# SCH_Patent-File_2025-01-08.net
KiCad netlist of a schematic drawn in EasyEDA
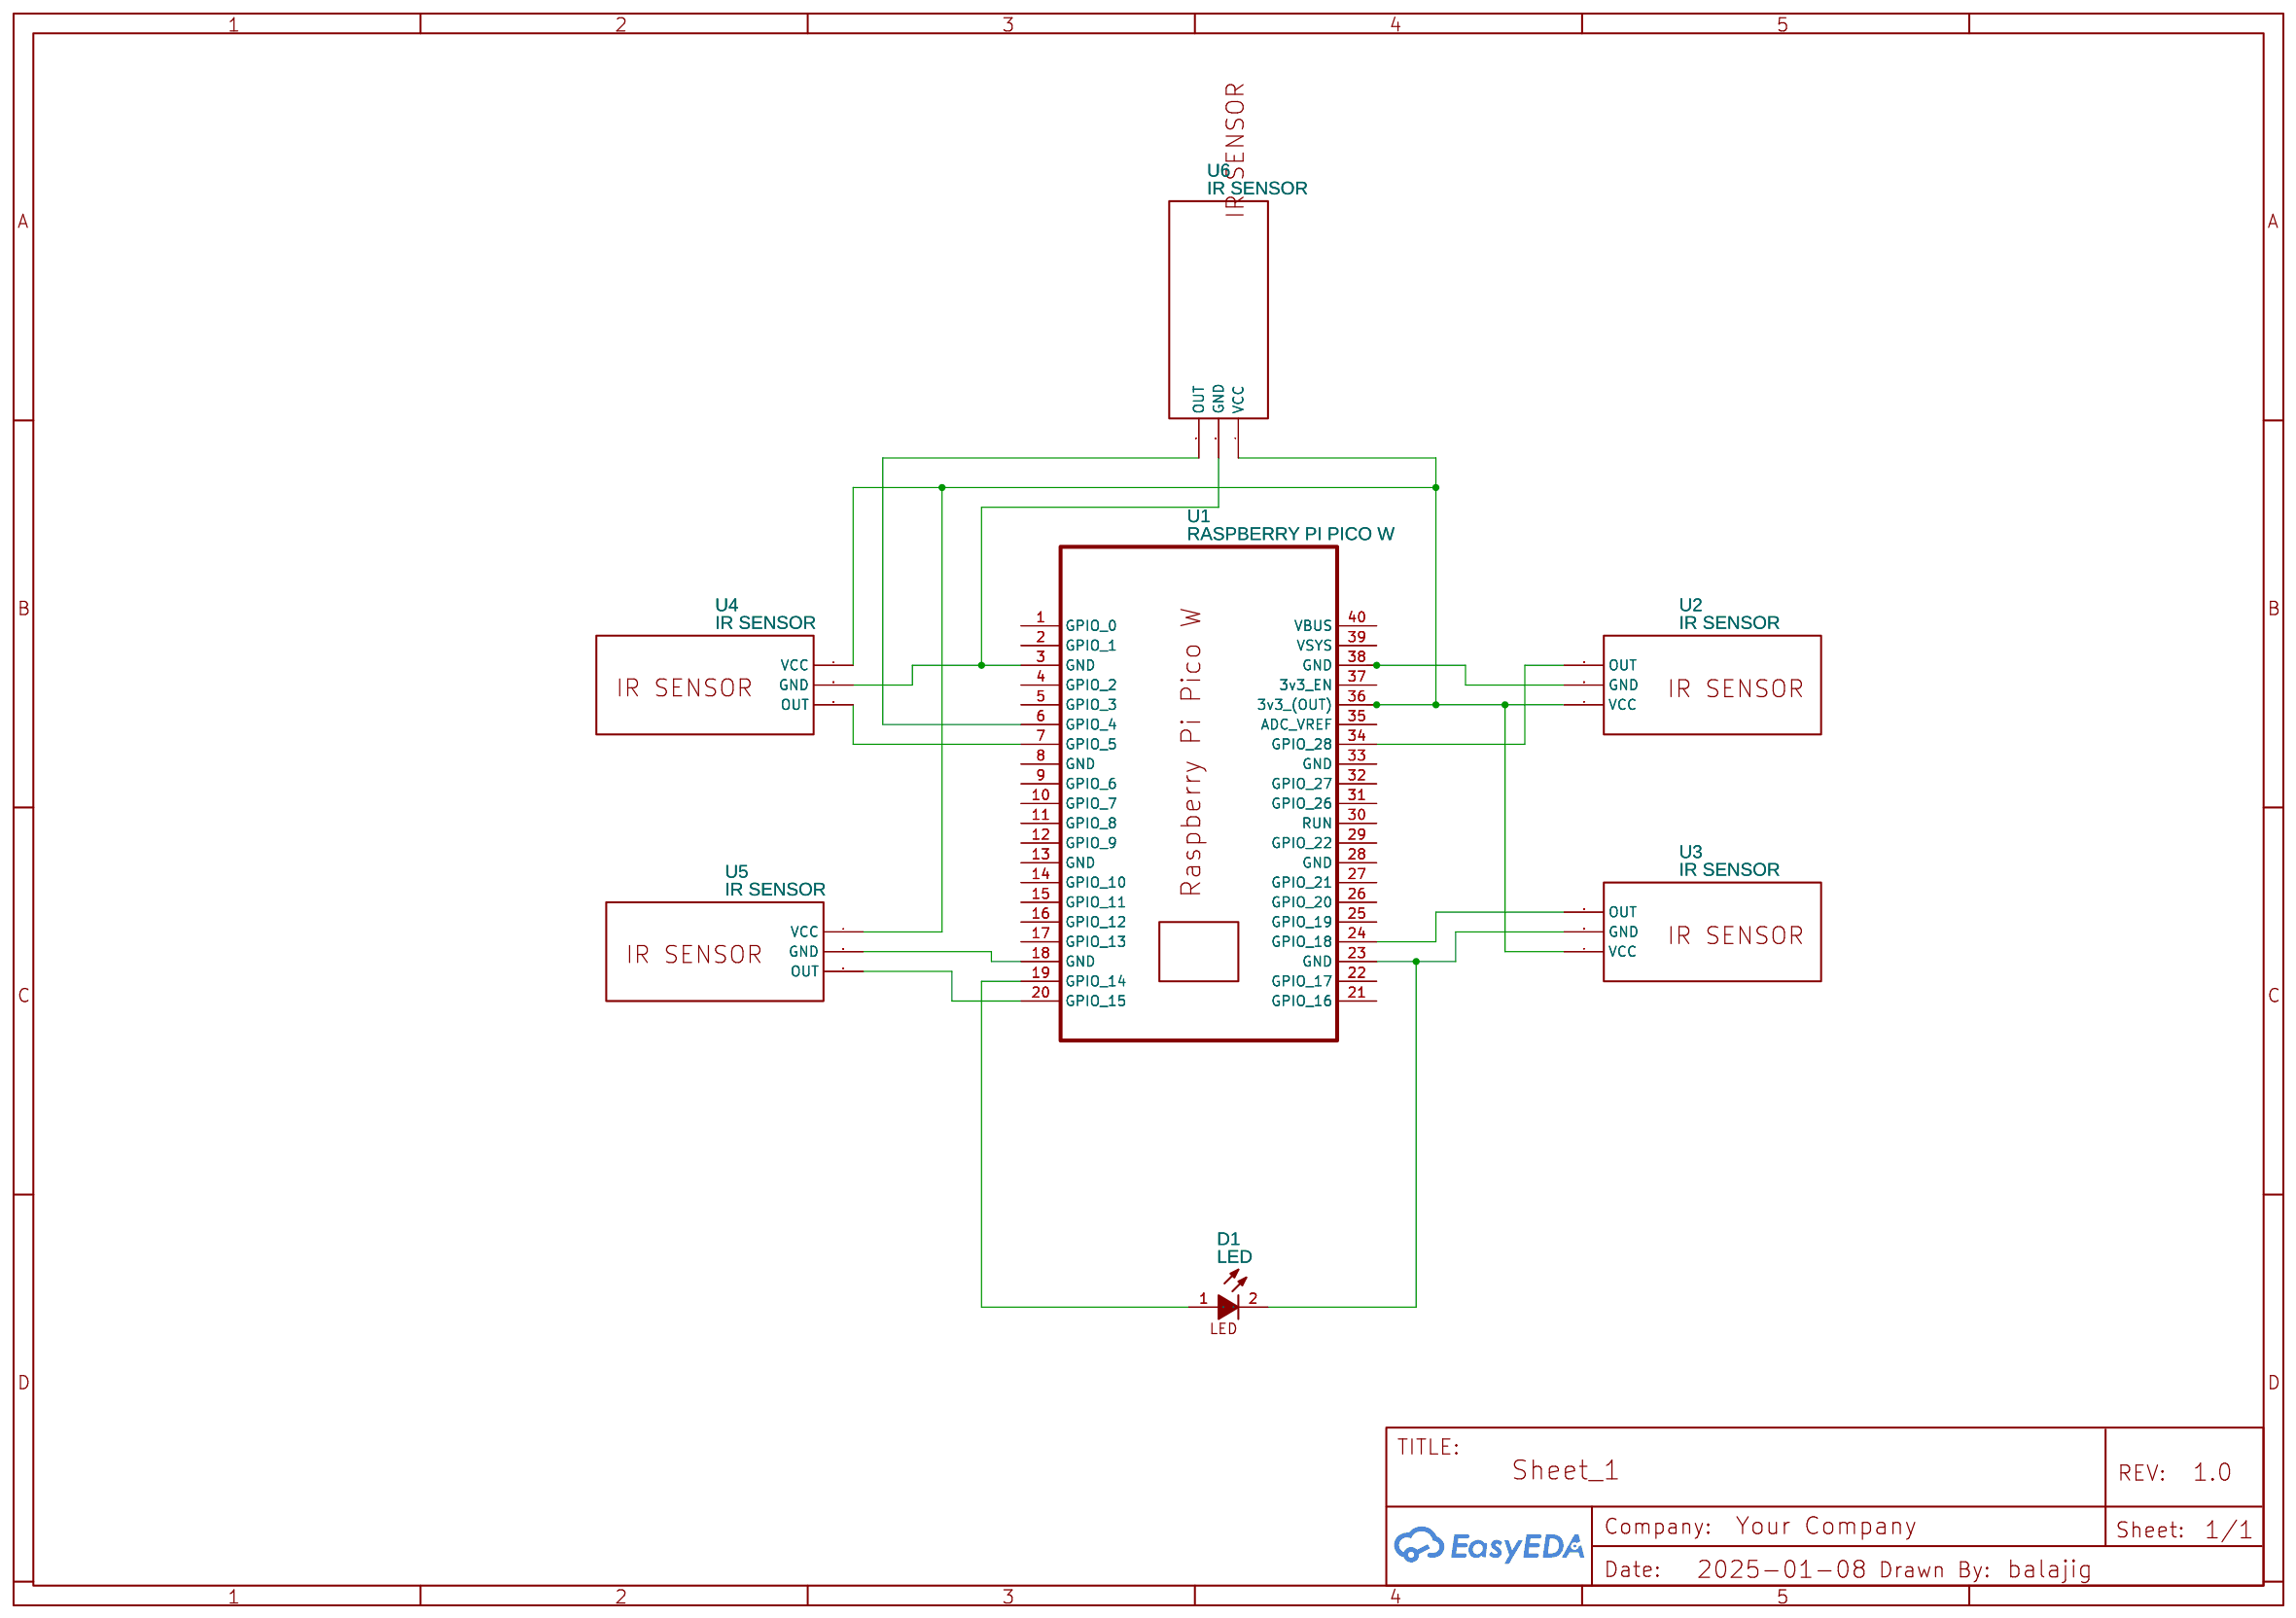
[diagram p0: schematic sheet]

(export (version "E")
  (design (tool "Eeschema 10.0.6"))
  (components
    (comp (ref "D1")
      (value "LED")
      (fields (field (name "Manufacturer Part") "5600") (field (name "Manufacturer") "VccLite"))
      (libsource (lib "") (part "LED"))
    )
    (comp (ref "U1") (value "RASPBERRY PI PICO W") (libsource (lib "") (part "RASPBERRY PI PICO W")))
    (comp (ref "U2") (value "IR SENSOR") (libsource (lib "") (part "MH-Sensor-Series Line Sensor_2")))
    (comp (ref "U3") (value "IR SENSOR") (libsource (lib "") (part "MH-Sensor-Series Line Sensor_2")))
    (comp (ref "U4") (value "IR SENSOR") (libsource (lib "") (part "MH-Sensor-Series Line Sensor")))
    (comp (ref "U5") (value "IR SENSOR") (libsource (lib "") (part "MH-Sensor-Series Line Sensor")))
    (comp (ref "U6") (value "IR SENSOR") (libsource (lib "") (part "MH-Sensor-Series Line Sensor_1")))
  )
  (nets
    (net (code "1") (name "Net-(D1-A)") (class "Default")
      (node (ref "D1") (pin "1") (pinfunction "A_1") (pintype "unspecified"))
      (node (ref "U1") (pin "19") (pinfunction "GPIO_14_19") (pintype "unspecified"))
    )
    (net (code "2") (name "Net-(D1-K)") (class "Default")
      (node (ref "D1") (pin "2") (pinfunction "K_2") (pintype "unspecified"))
      (node (ref "U1") (pin "23") (pinfunction "GND_23") (pintype "unspecified"))
      (node (ref "U3") (pin "3") (pinfunction "GND_3") (pintype "unspecified"))
    )
    (net (code "3") (name "Net-(U1-3v3_(OUT))") (class "Default")
      (node (ref "U1") (pin "36") (pinfunction "3v3_(OUT)_36") (pintype "unspecified"))
      (node (ref "U2") (pin "4") (pinfunction "VCC_4") (pintype "unspecified"))
      (node (ref "U3") (pin "4") (pinfunction "VCC_4") (pintype "unspecified"))
      (node (ref "U4") (pin "4") (pinfunction "VCC_4") (pintype "unspecified"))
      (node (ref "U5") (pin "4") (pinfunction "VCC_4") (pintype "unspecified"))
      (node (ref "U6") (pin "4") (pinfunction "VCC_4") (pintype "unspecified"))
    )
    (net (code "4") (name "Net-(U1-GPIO_4)") (class "Default")
      (node (ref "U1") (pin "6") (pinfunction "GPIO_4_6") (pintype "unspecified"))
      (node (ref "U6") (pin "2") (pinfunction "OUT_2") (pintype "unspecified"))
    )
    (net (code "5") (name "Net-(U1-GPIO_5)") (class "Default")
      (node (ref "U1") (pin "7") (pinfunction "GPIO_5_7") (pintype "unspecified"))
      (node (ref "U4") (pin "2") (pinfunction "OUT_2") (pintype "unspecified"))
    )
    (net (code "6") (name "Net-(U1-GPIO_15)") (class "Default")
      (node (ref "U1") (pin "20") (pinfunction "GPIO_15_20") (pintype "unspecified"))
      (node (ref "U5") (pin "2") (pinfunction "OUT_2") (pintype "unspecified"))
    )
    (net (code "7") (name "Net-(U1-GPIO_18)") (class "Default")
      (node (ref "U1") (pin "24") (pinfunction "GPIO_18_24") (pintype "unspecified"))
      (node (ref "U3") (pin "2") (pinfunction "OUT_2") (pintype "unspecified"))
    )
    (net (code "8") (name "Net-(U1-GPIO_28)") (class "Default")
      (node (ref "U1") (pin "34") (pinfunction "GPIO_28_34") (pintype "unspecified"))
      (node (ref "U2") (pin "2") (pinfunction "OUT_2") (pintype "unspecified"))
    )
    (net (code "9") (name "Net-(U2-GND)") (class "Default")
      (node (ref "U1") (pin "38") (pinfunction "GND_38") (pintype "unspecified"))
      (node (ref "U2") (pin "3") (pinfunction "GND_3") (pintype "unspecified"))
    )
    (net (code "10") (name "Net-(U4-GND)") (class "Default")
      (node (ref "U1") (pin "3") (pinfunction "GND_3") (pintype "unspecified"))
      (node (ref "U4") (pin "3") (pinfunction "GND_3") (pintype "unspecified"))
      (node (ref "U6") (pin "3") (pinfunction "GND_3") (pintype "unspecified"))
    )
    (net (code "11") (name "Net-(U5-GND)") (class "Default")
      (node (ref "U1") (pin "18") (pinfunction "GND_18") (pintype "unspecified"))
      (node (ref "U5") (pin "3") (pinfunction "GND_3") (pintype "unspecified"))
    )
    (net (code "12") (name "unconnected-(U1-3v3_EN-Pad37)") (class "Default")
      (node (ref "U1") (pin "37") (pinfunction "3v3_EN_37") (pintype "unspecified"))
    )
    (net (code "13") (name "unconnected-(U1-ADC_VREF-Pad35)") (class "Default")
      (node (ref "U1") (pin "35") (pinfunction "ADC_VREF_35") (pintype "unspecified"))
    )
    (net (code "14") (name "unconnected-(U1-GND-Pad8)") (class "Default")
      (node (ref "U1") (pin "8") (pinfunction "GND_8") (pintype "unspecified"))
    )
    (net (code "15") (name "unconnected-(U1-GND-Pad13)") (class "Default")
      (node (ref "U1") (pin "13") (pinfunction "GND_13") (pintype "unspecified"))
    )
    (net (code "16") (name "unconnected-(U1-GND-Pad28)") (class "Default")
      (node (ref "U1") (pin "28") (pinfunction "GND_28") (pintype "unspecified"))
    )
    (net (code "17") (name "unconnected-(U1-GND-Pad33)") (class "Default")
      (node (ref "U1") (pin "33") (pinfunction "GND_33") (pintype "unspecified"))
    )
    (net (code "18") (name "unconnected-(U1-GPIO_0-Pad1)") (class "Default")
      (node (ref "U1") (pin "1") (pinfunction "GPIO_0_1") (pintype "unspecified"))
    )
    (net (code "19") (name "unconnected-(U1-GPIO_1-Pad2)") (class "Default")
      (node (ref "U1") (pin "2") (pinfunction "GPIO_1_2") (pintype "unspecified"))
    )
    (net (code "20") (name "unconnected-(U1-GPIO_2-Pad4)") (class "Default")
      (node (ref "U1") (pin "4") (pinfunction "GPIO_2_4") (pintype "unspecified"))
    )
    (net (code "21") (name "unconnected-(U1-GPIO_3-Pad5)") (class "Default")
      (node (ref "U1") (pin "5") (pinfunction "GPIO_3_5") (pintype "unspecified"))
    )
    (net (code "22") (name "unconnected-(U1-GPIO_6-Pad9)") (class "Default")
      (node (ref "U1") (pin "9") (pinfunction "GPIO_6_9") (pintype "unspecified"))
    )
    (net (code "23") (name "unconnected-(U1-GPIO_7-Pad10)") (class "Default")
      (node (ref "U1") (pin "10") (pinfunction "GPIO_7_10") (pintype "unspecified"))
    )
    (net (code "24") (name "unconnected-(U1-GPIO_8-Pad11)") (class "Default")
      (node (ref "U1") (pin "11") (pinfunction "GPIO_8_11") (pintype "unspecified"))
    )
    (net (code "25") (name "unconnected-(U1-GPIO_9-Pad12)") (class "Default")
      (node (ref "U1") (pin "12") (pinfunction "GPIO_9_12") (pintype "unspecified"))
    )
    (net (code "26") (name "unconnected-(U1-GPIO_10-Pad14)") (class "Default")
      (node (ref "U1") (pin "14") (pinfunction "GPIO_10_14") (pintype "unspecified"))
    )
    (net (code "27") (name "unconnected-(U1-GPIO_11-Pad15)") (class "Default")
      (node (ref "U1") (pin "15") (pinfunction "GPIO_11_15") (pintype "unspecified"))
    )
    (net (code "28") (name "unconnected-(U1-GPIO_12-Pad16)") (class "Default")
      (node (ref "U1") (pin "16") (pinfunction "GPIO_12_16") (pintype "unspecified"))
    )
    (net (code "29") (name "unconnected-(U1-GPIO_13-Pad17)") (class "Default")
      (node (ref "U1") (pin "17") (pinfunction "GPIO_13_17") (pintype "unspecified"))
    )
    (net (code "30") (name "unconnected-(U1-GPIO_16-Pad21)") (class "Default")
      (node (ref "U1") (pin "21") (pinfunction "GPIO_16_21") (pintype "unspecified"))
    )
    (net (code "31") (name "unconnected-(U1-GPIO_17-Pad22)") (class "Default")
      (node (ref "U1") (pin "22") (pinfunction "GPIO_17_22") (pintype "unspecified"))
    )
    (net (code "32") (name "unconnected-(U1-GPIO_19-Pad25)") (class "Default")
      (node (ref "U1") (pin "25") (pinfunction "GPIO_19_25") (pintype "unspecified"))
    )
    (net (code "33") (name "unconnected-(U1-GPIO_20-Pad26)") (class "Default")
      (node (ref "U1") (pin "26") (pinfunction "GPIO_20_26") (pintype "unspecified"))
    )
    (net (code "34") (name "unconnected-(U1-GPIO_21-Pad27)") (class "Default")
      (node (ref "U1") (pin "27") (pinfunction "GPIO_21_27") (pintype "unspecified"))
    )
    (net (code "35") (name "unconnected-(U1-GPIO_22-Pad29)") (class "Default")
      (node (ref "U1") (pin "29") (pinfunction "GPIO_22_29") (pintype "unspecified"))
    )
    (net (code "36") (name "unconnected-(U1-GPIO_26-Pad31)") (class "Default")
      (node (ref "U1") (pin "31") (pinfunction "GPIO_26_31") (pintype "unspecified"))
    )
    (net (code "37") (name "unconnected-(U1-GPIO_27-Pad32)") (class "Default")
      (node (ref "U1") (pin "32") (pinfunction "GPIO_27_32") (pintype "unspecified"))
    )
    (net (code "38") (name "unconnected-(U1-RUN-Pad30)") (class "Default")
      (node (ref "U1") (pin "30") (pinfunction "RUN_30") (pintype "unspecified"))
    )
    (net (code "39") (name "unconnected-(U1-VBUS-Pad40)") (class "Default")
      (node (ref "U1") (pin "40") (pinfunction "VBUS_40") (pintype "unspecified"))
    )
    (net (code "40") (name "unconnected-(U1-VSYS-Pad39)") (class "Default")
      (node (ref "U1") (pin "39") (pinfunction "VSYS_39") (pintype "unspecified"))
    )
  )
)
